# Eload_Gen_3_Power_Module_-_User_Inferfac.net
KiCad netlist of a schematic drawn in Altium Designer
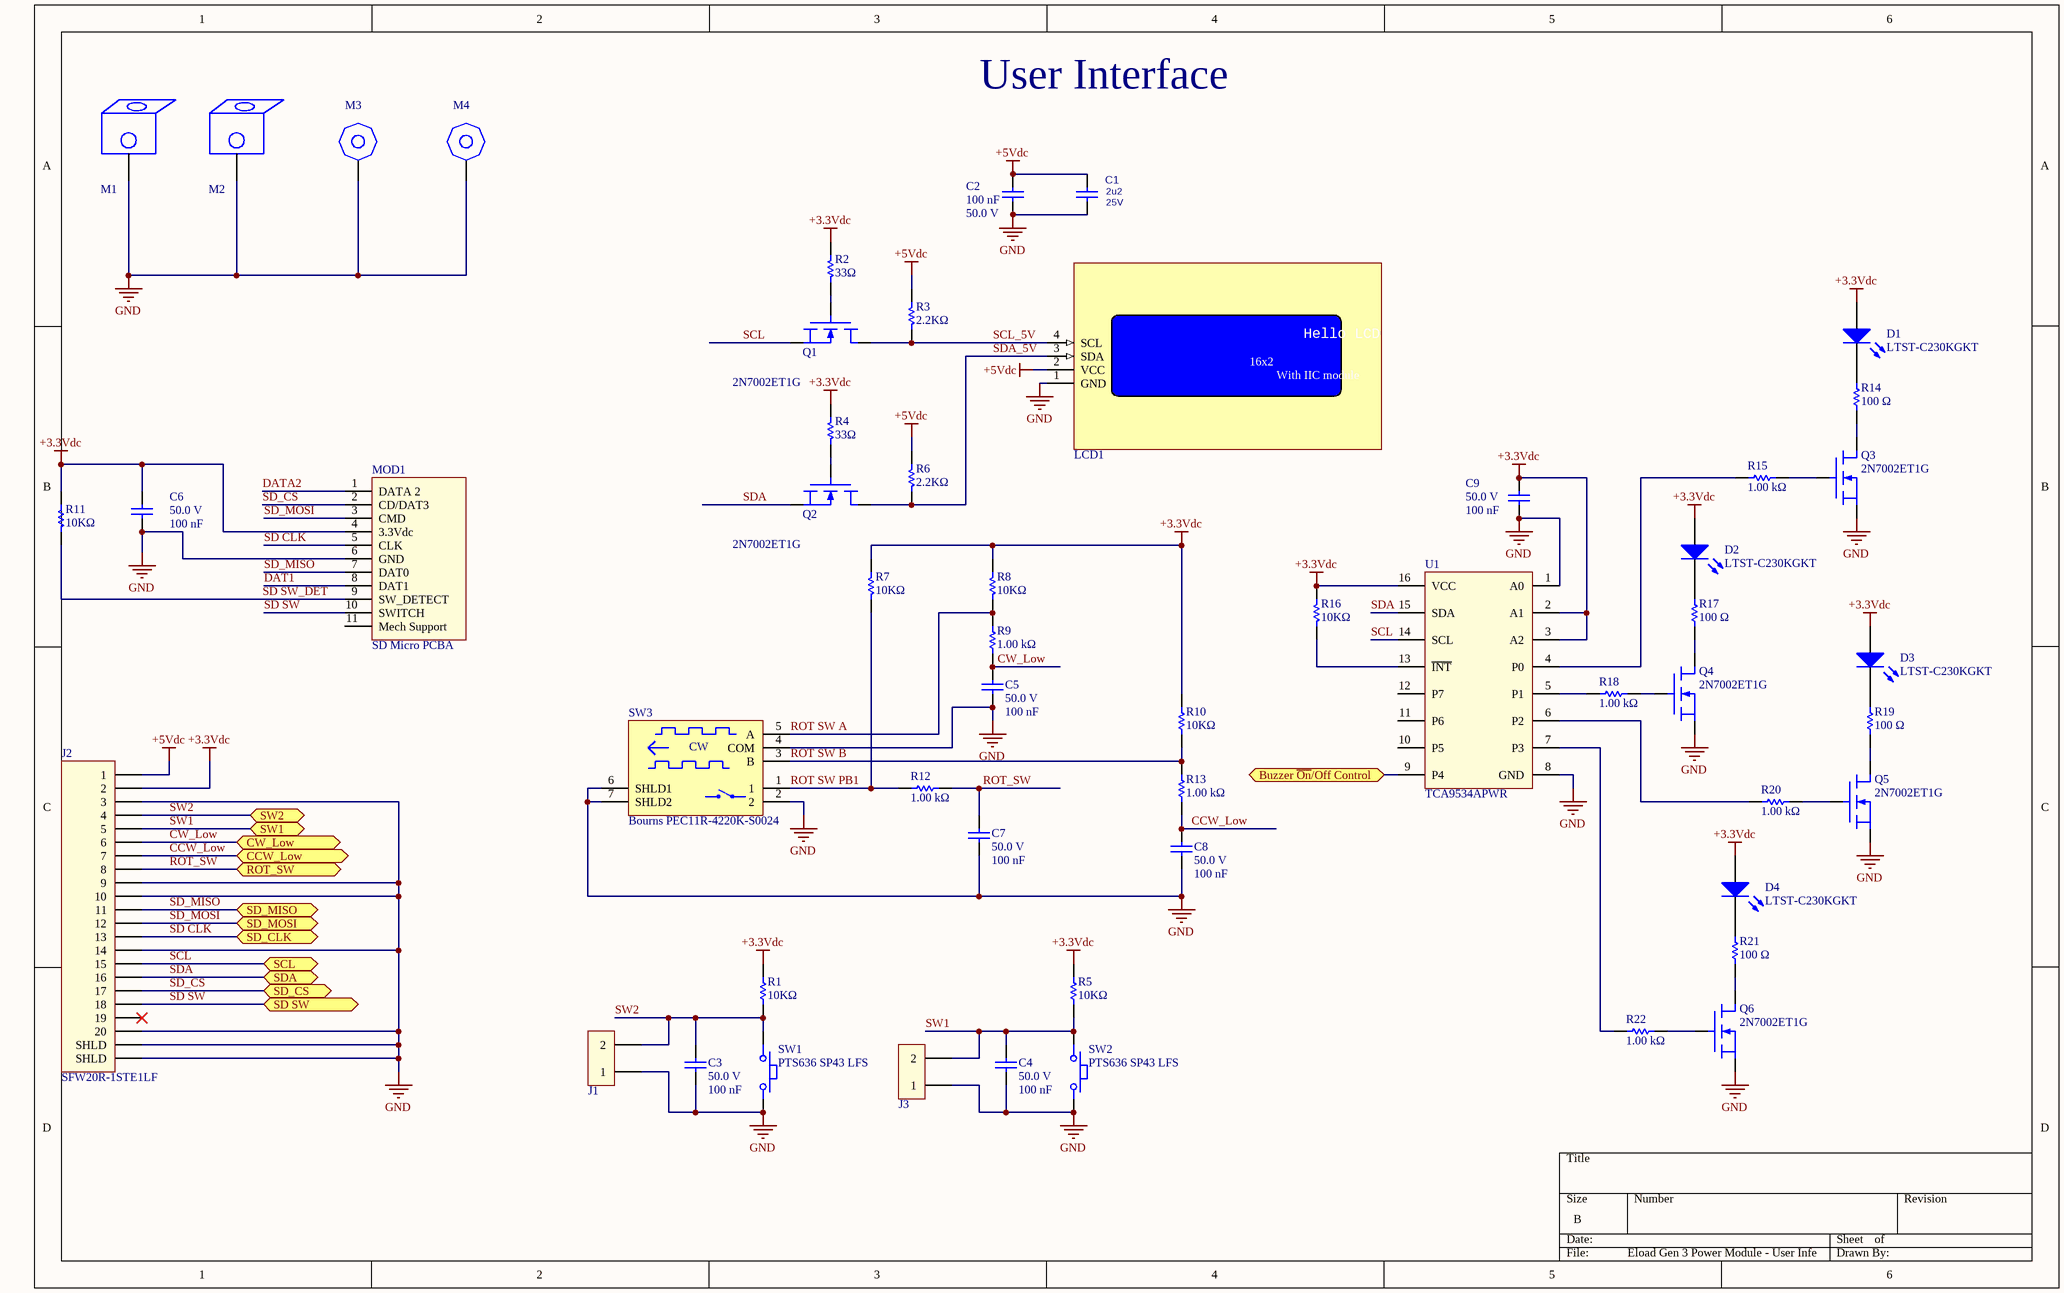
[diagram p0: Eload Gen 3 Power Module - User Inferface Rev 2.SchDoc]

(export (version "E")
  (design (tool "Eeschema 10.0.6"))
  (components
    (comp (ref "C1")
      (value "2u2")
      (footprint "CAP, 0805, HD")
      (description "Cap,SMD,MLCC,2.2uF 25V X7R 10%,0805")
      (fields (field (name "MANUFACTURER") "Murata") (field (name "VOLTAGE") "25V"))
      (libsource (lib "Master SEPT2019") (part "Cap,0805,2.2uF,10%,25V"))
    )
    (comp (ref "C2")
      (value "08055C104JAT2A")
      (footprint "Cap,0805")
      (description "Capacitor; Ceramic; Cap 0.1 uF; Tol 5%; Vol-Rtg 50 VDC; SMT; 0805; X7R; Tape & Reel")
      (fields (field (name "VOLTAGE RATING (DC)") "50.0 V") (field (name "CAPACITANCE") "100 nF"))
      (libsource (lib "Master JULY2019") (part "Cap,0805,100nf,50V,5%,08055C104JAT2A"))
    )
    (comp (ref "C3")
      (value "08055C104JAT2A")
      (footprint "CAP, 0805, HD")
      (description "Capacitor; Ceramic; Cap 0.1 uF; Tol 5%; Vol-Rtg 50 VDC; SMT; 0805; X7R; Tape & Reel")
      (fields (field (name "VOLTAGE RATING (DC)") "50.0 V") (field (name "CAPACITANCE") "100 nF"))
      (libsource (lib "Master JULY2019") (part "Cap,0805,100nf,50V,5%,08055C104JAT2A"))
    )
    (comp (ref "C4")
      (value "08055C104JAT2A")
      (footprint "CAP, 0805, HD")
      (description "Capacitor; Ceramic; Cap 0.1 uF; Tol 5%; Vol-Rtg 50 VDC; SMT; 0805; X7R; Tape & Reel")
      (fields (field (name "VOLTAGE RATING (DC)") "50.0 V") (field (name "CAPACITANCE") "100 nF"))
      (libsource (lib "Master JULY2019") (part "Cap,0805,100nf,50V,5%,08055C104JAT2A"))
    )
    (comp (ref "C5")
      (value "08055C104JAT2A")
      (footprint "CAP, 0805, HD")
      (description "Capacitor; Ceramic; Cap 0.1 uF; Tol 5%; Vol-Rtg 50 VDC; SMT; 0805; X7R; Tape & Reel")
      (fields (field (name "VOLTAGE RATING (DC)") "50.0 V") (field (name "CAPACITANCE") "100 nF"))
      (libsource (lib "Master JULY2019") (part "Cap,0805,100nf,50V,5%,08055C104JAT2A"))
    )
    (comp (ref "C6")
      (value "08055C104JAT2A")
      (footprint "Cap,0805")
      (description "Capacitor; Ceramic; Cap 0.1 uF; Tol 5%; Vol-Rtg 50 VDC; SMT; 0805; X7R; Tape & Reel")
      (fields (field (name "VOLTAGE RATING (DC)") "50.0 V") (field (name "CAPACITANCE") "100 nF"))
      (libsource (lib "Master JULY2019") (part "Cap,0805,100nf,50V,5%,08055C104JAT2A"))
    )
    (comp (ref "C7")
      (value "08055C104JAT2A")
      (footprint "CAP, 0805, HD")
      (description "Capacitor; Ceramic; Cap 0.1 uF; Tol 5%; Vol-Rtg 50 VDC; SMT; 0805; X7R; Tape & Reel")
      (fields (field (name "VOLTAGE RATING (DC)") "50.0 V") (field (name "CAPACITANCE") "100 nF"))
      (libsource (lib "Master JULY2019") (part "Cap,0805,100nf,50V,5%,08055C104JAT2A"))
    )
    (comp (ref "C8")
      (value "08055C104JAT2A")
      (footprint "CAP, 0805, HD")
      (description "Capacitor; Ceramic; Cap 0.1 uF; Tol 5%; Vol-Rtg 50 VDC; SMT; 0805; X7R; Tape & Reel")
      (fields (field (name "VOLTAGE RATING (DC)") "50.0 V") (field (name "CAPACITANCE") "100 nF"))
      (libsource (lib "Master JULY2019") (part "Cap,0805,100nf,50V,5%,08055C104JAT2A"))
    )
    (comp (ref "C9")
      (value "08055C104JAT2A")
      (footprint "Cap,0805")
      (description "Capacitor; Ceramic; Cap 0.1 uF; Tol 5%; Vol-Rtg 50 VDC; SMT; 0805; X7R; Tape & Reel")
      (fields (field (name "VOLTAGE RATING (DC)") "50.0 V") (field (name "CAPACITANCE") "100 nF"))
      (libsource (lib "Master Mar2021") (part "Cap,0805,100nf,50V,5%,08055C104JAT2A"))
    )
    (comp (ref "D1")
      (value "LTST-C230KGKT")
      (footprint "LED,SMD,Bottom Entry,1206")
      (description "LED GREEN CLEAR CHIP SMD")
      (fields (field (name "MANUFACTURER") "Lite-On Inc."))
      (libsource (lib "Master JULY2019") (part "LED,1206,Green,SMD,BtmEnt,LTST-C230KGKT"))
    )
    (comp (ref "D2")
      (value "LTST-C230KGKT")
      (footprint "LED,SMD,Bottom Entry,1206")
      (description "LED GREEN CLEAR CHIP SMD")
      (fields (field (name "MANUFACTURER") "Lite-On Inc."))
      (libsource (lib "Master JULY2019") (part "LED,1206,Green,SMD,BtmEnt,LTST-C230KGKT"))
    )
    (comp (ref "D3")
      (value "LTST-C230KGKT")
      (footprint "LED,SMD,Bottom Entry,1206")
      (description "LED GREEN CLEAR CHIP SMD")
      (fields (field (name "MANUFACTURER") "Lite-On Inc."))
      (libsource (lib "Master JULY2019") (part "LED,1206,Green,SMD,BtmEnt,LTST-C230KGKT"))
    )
    (comp (ref "D4")
      (value "LTST-C230KGKT")
      (footprint "LED,SMD,Bottom Entry,1206")
      (description "LED GREEN CLEAR CHIP SMD")
      (fields (field (name "MANUFACTURER") "Lite-On Inc."))
      (libsource (lib "Master JULY2019") (part "LED,1206,Green,SMD,BtmEnt,LTST-C230KGKT"))
    )
    (comp (ref "J1")
      (value "Generic Header")
      (footprint "HEADER-1X2,0.1\"")
      (libsource (lib "Master JULY2019") (part "Header 1x2,0.1{dblquote}Spacing"))
    )
    (comp (ref "J2")
      (value "SFW20R-1STE1LF")
      (footprint "Connector,FlatFlex,20Pin,RA")
      (description "CONN FFC BOTTOM 20POS 1.00MM R/A")
      (fields (field (name "MANUFACTURER") "Amphenol ICC (FCI)"))
      (libsource (lib "Master JULY2019") (part "Connector,FFC,SMD,20Pin,1mmSpc,SFW20R-1STE1LF"))
    )
    (comp (ref "J3")
      (value "Generic Header")
      (footprint "HEADER-1X2,0.1\"")
      (libsource (lib "Master JULY2019") (part "Header 1x2,0.1{dblquote}Spacing"))
    )
    (comp (ref "LCD1")
      (value "LCD, 20x4")
      (footprint "LCD Module 16x2 - IIC MOD")
      (description "LCD Character Display; 4x20 Char.; 98x60; STN- BLUE; Transmissive; 8-Bit Parallel")
      (libsource (lib "Master JULY2019") (part "LCD, 16x2, IIC"))
    )
    (comp (ref "M1")
      (value "4334")
      (footprint "Mech,Bracket,RA,#6,Threaded")
      (description "Mounting Bracket Short L #6-32 (2) Steel, Nickel Plated")
      (fields (field (name "MANUFACTURER") "Keystone Electronics"))
      (libsource (lib "Master JULY2019") (part "Mech,Bracket,RA,Threaded,4334"))
    )
    (comp (ref "M2")
      (value "4334")
      (footprint "Mech,Bracket,RA,#6,Threaded")
      (description "Mounting Bracket Short L #6-32 (2) Steel, Nickel Plated")
      (fields (field (name "MANUFACTURER") "Keystone Electronics"))
      (libsource (lib "Master JULY2019") (part "Mech,Bracket,RA,Threaded,4334"))
    )
    (comp (ref "M3")
      (value "M3 hex Standoff")
      (footprint "Standoff,Hex,M3,8mm")
      (description "HEX STANDOFF M3,generic")
      (libsource (lib "Master JULY2019") (part "Mech,Standoff, M3, Hex"))
    )
    (comp (ref "M4")
      (value "M3 hex Standoff")
      (footprint "Standoff,Hex,M3,8mm")
      (description "HEX STANDOFF M3,generic")
      (libsource (lib "Master JULY2019") (part "Mech,Standoff, M3, Hex"))
    )
    (comp (ref "MOD1")
      (value "SD Card Connector Breakout")
      (footprint "Mod, SD Card Connector Breakout")
      (fields (field (name "DISCRIPTION") "SD Micro PCBA"))
      (libsource (lib "Master JULY2019") (part "Mod,SD Card breakout, Vertical"))
    )
    (comp (ref "Q1")
      (value "2N7002ET1G")
      (footprint "SOT23-3")
      (description "Small Signal MOSFET, 60 V, 310 mA, Single, N-Channel, 3-Pin SOT-23, Pb-Free, Tape and Reel")
      (fields
        (field (name "MANUFACTURER") "ON Semiconductor")
        (field (name "MANUFACTURER PART NUMBER") "2N7002ET1G")
      )
      (libsource (lib "Master JULY2019") (part "MOSFET,N-Channel,SOT23,0.25A,60V,2N7002ET1G"))
    )
    (comp (ref "Q2")
      (value "2N7002ET1G")
      (footprint "SOT23-3")
      (description "Small Signal MOSFET, 60 V, 310 mA, Single, N-Channel, 3-Pin SOT-23, Pb-Free, Tape and Reel")
      (fields
        (field (name "MANUFACTURER") "ON Semiconductor")
        (field (name "MANUFACTURER PART NUMBER") "2N7002ET1G")
      )
      (libsource (lib "Master JULY2019") (part "MOSFET,N-Channel,SOT23,0.25A,60V,2N7002ET1G"))
    )
    (comp (ref "Q3")
      (value "2N7002ET1G")
      (footprint "SOT23-3")
      (description "Small Signal MOSFET, 60 V, 310 mA, Single, N-Channel, 3-Pin SOT-23, Pb-Free, Tape and Reel")
      (fields
        (field (name "MANUFACTURER") "ON Semiconductor")
        (field (name "MANUFACTURER PART NUMBER") "2N7002ET1G")
      )
      (libsource (lib "Master JULY2019") (part "MOSFET,N-Channel,SOT23,0.25A,60V,2N7002ET1G"))
    )
    (comp (ref "Q4")
      (value "2N7002ET1G")
      (footprint "SOT23-3")
      (description "Small Signal MOSFET, 60 V, 310 mA, Single, N-Channel, 3-Pin SOT-23, Pb-Free, Tape and Reel")
      (fields
        (field (name "MANUFACTURER") "ON Semiconductor")
        (field (name "MANUFACTURER PART NUMBER") "2N7002ET1G")
      )
      (libsource (lib "Master JULY2019") (part "MOSFET,N-Channel,SOT23,0.25A,60V,2N7002ET1G"))
    )
    (comp (ref "Q5")
      (value "2N7002ET1G")
      (footprint "SOT23-3")
      (description "Small Signal MOSFET, 60 V, 310 mA, Single, N-Channel, 3-Pin SOT-23, Pb-Free, Tape and Reel")
      (fields
        (field (name "MANUFACTURER") "ON Semiconductor")
        (field (name "MANUFACTURER PART NUMBER") "2N7002ET1G")
      )
      (libsource (lib "Master JULY2019") (part "MOSFET,N-Channel,SOT23,0.25A,60V,2N7002ET1G"))
    )
    (comp (ref "Q6")
      (value "2N7002ET1G")
      (footprint "SOT23-3")
      (description "Small Signal MOSFET, 60 V, 310 mA, Single, N-Channel, 3-Pin SOT-23, Pb-Free, Tape and Reel")
      (fields
        (field (name "MANUFACTURER") "ON Semiconductor")
        (field (name "MANUFACTURER PART NUMBER") "2N7002ET1G")
      )
      (libsource (lib "Master JULY2019") (part "MOSFET,N-Channel,SOT23,0.25A,60V,2N7002ET1G"))
    )
    (comp (ref "R1")
      (value "Vishay / Dale CRCW080510K0FKTA")
      (footprint "res, 0805, HD")
      (description "RES SMD 10K OHM 1% 1/8W 0805")
      (fields (field (name "RESISTANCE") "10KΩ"))
      (libsource (lib "Master JULY2019") (part "Res,0805,10.0kΩ,1%,100 ppm,CRCW080510K0FKTA"))
    )
    (comp (ref "R2")
      (value "CR0805-JW-330ELF")
      (footprint "res, 0805, HD")
      (description "RES SMD 33 OHM 5% 1/8W 0805")
      (fields
        (field (name "MANUFACTURER") "Bourns Inc.")
        (field (name "TOLERANCE") "±5%")
        (field (name "RESISTANCE") "33Ω")
      )
      (libsource (lib "Master JULY2019") (part "Res,0805,33Ω,±5%,200ppm,CR0805-JW-330ELF"))
    )
    (comp (ref "R3")
      (value "CRCW08052K20FKEA")
      (footprint "res, 0805, HD")
      (description "RES SMD 2.2K OHM 1% 1/8W 0805")
      (fields (field (name "RESISTANCE") "2.2KΩ"))
      (libsource (lib "Master JULY2019") (part "Res,0805,2.2KΩ,±1%,100.0 ppm/°C,150.0 V,CRCW08052K20FKEA"))
    )
    (comp (ref "R4")
      (value "CR0805-JW-330ELF")
      (footprint "res, 0805, HD")
      (description "RES SMD 33 OHM 5% 1/8W 0805")
      (fields
        (field (name "MANUFACTURER") "Bourns Inc.")
        (field (name "TOLERANCE") "±5%")
        (field (name "RESISTANCE") "33Ω")
      )
      (libsource (lib "Master JULY2019") (part "Res,0805,33Ω,±5%,200ppm,CR0805-JW-330ELF"))
    )
    (comp (ref "R5")
      (value "Vishay / Dale CRCW080510K0FKTA")
      (footprint "res, 0805, HD")
      (description "RES SMD 10K OHM 1% 1/8W 0805")
      (fields (field (name "RESISTANCE") "10KΩ"))
      (libsource (lib "Master JULY2019") (part "Res,0805,10.0kΩ,1%,100 ppm,CRCW080510K0FKTA"))
    )
    (comp (ref "R6")
      (value "CRCW08052K20FKEA")
      (footprint "res, 0805, HD")
      (description "RES SMD 2.2K OHM 1% 1/8W 0805")
      (fields (field (name "RESISTANCE") "2.2KΩ"))
      (libsource (lib "Master JULY2019") (part "Res,0805,2.2KΩ,±1%,100.0 ppm/°C,150.0 V,CRCW08052K20FKEA"))
    )
    (comp (ref "R7")
      (value "Vishay / Dale CRCW080510K0FKTA")
      (footprint "res, 0805, HD")
      (description "RES SMD 10K OHM 1% 1/8W 0805")
      (fields (field (name "RESISTANCE") "10KΩ"))
      (libsource (lib "Master JULY2019") (part "Res,0805,10.0kΩ,1%,100 ppm,CRCW080510K0FKTA"))
    )
    (comp (ref "R8")
      (value "Vishay / Dale CRCW080510K0FKTA")
      (footprint "res, 0805, HD")
      (description "RES SMD 10K OHM 1% 1/8W 0805")
      (fields (field (name "RESISTANCE") "10KΩ"))
      (libsource (lib "Master JULY2019") (part "Res,0805,10.0kΩ,1%,100 ppm,CRCW080510K0FKTA"))
    )
    (comp (ref "R9")
      (value "Vishay CRCW08051K00JNEA")
      (footprint "res, 0805, HD")
      (description "Res Thick Film 0805 1K Ohm 5% 0.125W(1/8W) ±200ppm/C Molded SMD Automotive Paper T/R")
      (fields
        (field (name "MANUFACTURER PART NUMBER") "CRCW08051K00JNEA")
        (field (name "RESISTANCE") "1.00 kΩ")
      )
      (libsource (lib "Master JULY2019") (part "Res,0805,1.00 kΩ,5%,200ppm,CRCW08051K00JNEA"))
    )
    (comp (ref "R10")
      (value "Vishay / Dale CRCW080510K0FKTA")
      (footprint "res, 0805, HD")
      (description "RES SMD 10K OHM 1% 1/8W 0805")
      (fields (field (name "RESISTANCE") "10KΩ"))
      (libsource (lib "Master JULY2019") (part "Res,0805,10.0kΩ,1%,100 ppm,CRCW080510K0FKTA"))
    )
    (comp (ref "R11")
      (value "Vishay / Dale CRCW080510K0FKTA")
      (footprint "res, 0805, HD")
      (description "RES SMD 10K OHM 1% 1/8W 0805")
      (fields (field (name "RESISTANCE") "10KΩ"))
      (libsource (lib "Master JULY2019") (part "Res,0805,10.0kΩ,1%,100 ppm,CRCW080510K0FKTA"))
    )
    (comp (ref "R12")
      (value "Vishay CRCW08051K00JNEA")
      (footprint "res, 0805, HD")
      (description "Res Thick Film 0805 1K Ohm 5% 0.125W(1/8W) ±200ppm/C Molded SMD Automotive Paper T/R")
      (fields
        (field (name "MANUFACTURER PART NUMBER") "CRCW08051K00JNEA")
        (field (name "RESISTANCE") "1.00 kΩ")
      )
      (libsource (lib "Master JULY2019") (part "Res,0805,1.00 kΩ,5%,200ppm,CRCW08051K00JNEA"))
    )
    (comp (ref "R13")
      (value "Vishay CRCW08051K00JNEA")
      (footprint "res, 0805, HD")
      (description "Res Thick Film 0805 1K Ohm 5% 0.125W(1/8W) ±200ppm/C Molded SMD Automotive Paper T/R")
      (fields
        (field (name "MANUFACTURER PART NUMBER") "CRCW08051K00JNEA")
        (field (name "RESISTANCE") "1.00 kΩ")
      )
      (libsource (lib "Master JULY2019") (part "Res,0805,1.00 kΩ,5%,200ppm,CRCW08051K00JNEA"))
    )
    (comp (ref "R14")
      (value "CRCW0805100RJNEAC")
      (footprint "res, 0805, HD")
      (description "RES 100 OHM 5% 1/8W 0805")
      (fields (field (name "TOLERANCE") "±5%") (field (name "RESISTANCE") "100 Ω"))
      (libsource (lib "Master JULY2019") (part "Res,0805,100Ω,5%,±200ppm/°C"))
    )
    (comp (ref "R15")
      (value "Vishay CRCW08051K00JNEA")
      (footprint "res, 0805, HD")
      (description "Res Thick Film 0805 1K Ohm 5% 0.125W(1/8W) ±200ppm/C Molded SMD Automotive Paper T/R")
      (fields
        (field (name "MANUFACTURER PART NUMBER") "CRCW08051K00JNEA")
        (field (name "RESISTANCE") "1.00 kΩ")
      )
      (libsource (lib "Master JULY2019") (part "Res,0805,1.00 kΩ,5%,200ppm,CRCW08051K00JNEA"))
    )
    (comp (ref "R16")
      (value "Vishay / Dale CRCW080510K0FKTA")
      (footprint "res, 0805, HD")
      (description "RES SMD 10K OHM 1% 1/8W 0805")
      (fields (field (name "RESISTANCE") "10KΩ"))
      (libsource (lib "Master Mar2021") (part "Res,0805,10.0kΩ,1%,100 ppm,CRCW080510K0FKTA"))
    )
    (comp (ref "R17")
      (value "CRCW0805100RJNEAC")
      (footprint "res, 0805, HD")
      (description "RES 100 OHM 5% 1/8W 0805")
      (fields (field (name "TOLERANCE") "±5%") (field (name "RESISTANCE") "100 Ω"))
      (libsource (lib "Master JULY2019") (part "Res,0805,100Ω,5%,±200ppm/°C"))
    )
    (comp (ref "R18")
      (value "Vishay CRCW08051K00JNEA")
      (footprint "res, 0805, HD")
      (description "Res Thick Film 0805 1K Ohm 5% 0.125W(1/8W) ±200ppm/C Molded SMD Automotive Paper T/R")
      (fields
        (field (name "MANUFACTURER PART NUMBER") "CRCW08051K00JNEA")
        (field (name "RESISTANCE") "1.00 kΩ")
      )
      (libsource (lib "Master Mar2021") (part "Res,0805,1.00 kΩ,5%,200ppm,CRCW08051K00JNEA"))
    )
    (comp (ref "R19")
      (value "CRCW0805100RJNEAC")
      (footprint "res, 0805, HD")
      (description "RES 100 OHM 5% 1/8W 0805")
      (fields (field (name "TOLERANCE") "±5%") (field (name "RESISTANCE") "100 Ω"))
      (libsource (lib "Master JULY2019") (part "Res,0805,100Ω,5%,±200ppm/°C"))
    )
    (comp (ref "R20")
      (value "Vishay CRCW08051K00JNEA")
      (footprint "res, 0805, HD")
      (description "Res Thick Film 0805 1K Ohm 5% 0.125W(1/8W) ±200ppm/C Molded SMD Automotive Paper T/R")
      (fields
        (field (name "MANUFACTURER PART NUMBER") "CRCW08051K00JNEA")
        (field (name "RESISTANCE") "1.00 kΩ")
      )
      (libsource (lib "Master JULY2019") (part "Res,0805,1.00 kΩ,5%,200ppm,CRCW08051K00JNEA"))
    )
    (comp (ref "R21")
      (value "CRCW0805100RJNEAC")
      (footprint "res, 0805, HD")
      (description "RES 100 OHM 5% 1/8W 0805")
      (fields (field (name "TOLERANCE") "±5%") (field (name "RESISTANCE") "100 Ω"))
      (libsource (lib "Master JULY2019") (part "Res,0805,100Ω,5%,±200ppm/°C"))
    )
    (comp (ref "R22")
      (value "Vishay CRCW08051K00JNEA")
      (footprint "res, 0805, HD")
      (description "Res Thick Film 0805 1K Ohm 5% 0.125W(1/8W) ±200ppm/C Molded SMD Automotive Paper T/R")
      (fields
        (field (name "MANUFACTURER PART NUMBER") "CRCW08051K00JNEA")
        (field (name "RESISTANCE") "1.00 kΩ")
      )
      (libsource (lib "Master JULY2019") (part "Res,0805,1.00 kΩ,5%,200ppm,CRCW08051K00JNEA"))
    )
    (comp (ref "SW1")
      (value "PTS636 SP43 LFS")
      (footprint "PTS636 SP43 LFS")
      (description "Tactile Switch SPST-NO Top Actuated Through Hole")
      (fields (field (name "MANUFACTURER") "C&K"))
      (libsource (lib "Master JULY2019") (part "Switch,Through Hole,Tactile,SPST-NO,PTS636 SP43 LFS"))
    )
    (comp (ref "SW2")
      (value "PTS636 SP43 LFS")
      (footprint "PTS636 SP43 LFS")
      (description "Tactile Switch SPST-NO Top Actuated Through Hole")
      (fields (field (name "MANUFACTURER") "C&K"))
      (libsource (lib "Master JULY2019") (part "Switch,Through Hole,Tactile,SPST-NO,PTS636 SP43 LFS"))
    )
    (comp (ref "SW3")
      (value "Bourns PEC11R-4220K-S0024")
      (footprint "Rotary encoder")
      (description "24 Pulse Incremental Mechanical Rotary Encoder w/ 6 mm Knurl Shaft, Through Hole")
      (libsource (lib "Master JULY2019") (part "Rotary encoder, PEC11R-4220K-S0024"))
    )
    (comp (ref "U1")
      (value "TCA9534APWR")
      (footprint "TSSOP-16")
      (description "IC I/O EXPANDER I2C 8B 16TSSOP")
      (fields (field (name "MANUFACTURER") "Texas Instruments") (field (name "BASE PART NUMBER") "TCA953"))
      (libsource (lib "Master Mar2021") (part "IC,IO Expander,IIC,8IO,16-TSSOP,TCA9534APWR"))
    )
  )
  (nets
    (net (code "1") (name "+3.3Vdc") (class "Default")
      (node (ref "C6") (pin "2") (pinfunction "2_2") (pintype "passive"))
      (node (ref "C9") (pin "2") (pinfunction "2_2") (pintype "passive"))
      (node (ref "D1") (pin "2") (pinfunction "A_2") (pintype "passive"))
      (node (ref "D2") (pin "2") (pinfunction "A_2") (pintype "passive"))
      (node (ref "D3") (pin "2") (pinfunction "A_2") (pintype "passive"))
      (node (ref "D4") (pin "2") (pinfunction "A_2") (pintype "passive"))
      (node (ref "J2") (pin "2") (pinfunction "2_2") (pintype "passive"))
      (node (ref "MOD1") (pin "4") (pinfunction "3.3Vdc_4") (pintype "passive"))
      (node (ref "R1") (pin "1") (pinfunction "1_1") (pintype "passive"))
      (node (ref "R10") (pin "1") (pinfunction "1_1") (pintype "passive"))
      (node (ref "R11") (pin "1") (pinfunction "1_1") (pintype "passive"))
      (node (ref "R16") (pin "2") (pinfunction "2_2") (pintype "passive"))
      (node (ref "R2") (pin "1") (pinfunction "1_1") (pintype "passive"))
      (node (ref "R4") (pin "1") (pinfunction "1_1") (pintype "passive"))
      (node (ref "R5") (pin "1") (pinfunction "1_1") (pintype "passive"))
      (node (ref "R7") (pin "2") (pinfunction "2_2") (pintype "passive"))
      (node (ref "R8") (pin "2") (pinfunction "2_2") (pintype "passive"))
      (node (ref "U1") (pin "16") (pinfunction "VCC_16") (pintype "passive"))
      (node (ref "U1") (pin "2") (pinfunction "A1_2") (pintype "passive"))
      (node (ref "U1") (pin "3") (pinfunction "A2_3") (pintype "passive"))
    )
    (net (code "2") (name "+5Vdc") (class "Default")
      (node (ref "C1") (pin "2") (pintype "passive"))
      (node (ref "C2") (pin "2") (pinfunction "2_2") (pintype "passive"))
      (node (ref "J2") (pin "1") (pinfunction "1_1") (pintype "passive"))
      (node (ref "LCD1") (pin "2") (pinfunction "VCC_2") (pintype "power_in"))
      (node (ref "R3") (pin "2") (pinfunction "2_2") (pintype "passive"))
      (node (ref "R6") (pin "2") (pinfunction "2_2") (pintype "passive"))
    )
    (net (code "3") (name "/Buzzer ~{On}{slash}Off Control") (class "Default")
      (node (ref "U1") (pin "9") (pinfunction "P4_9") (pintype "passive"))
    )
    (net (code "4") (name "/CCW_Low") (class "Default")
      (node (ref "C8") (pin "2") (pinfunction "2_2") (pintype "passive"))
      (node (ref "J2") (pin "7") (pinfunction "7_7") (pintype "passive"))
      (node (ref "R13") (pin "2") (pinfunction "2_2") (pintype "passive"))
    )
    (net (code "5") (name "/CW_Low") (class "Default")
      (node (ref "C5") (pin "2") (pinfunction "2_2") (pintype "passive"))
      (node (ref "J2") (pin "6") (pinfunction "6_6") (pintype "passive"))
      (node (ref "R9") (pin "2") (pinfunction "2_2") (pintype "passive"))
    )
    (net (code "6") (name "/DAT1") (class "Default")
      (node (ref "MOD1") (pin "8") (pinfunction "DAT1_8") (pintype "passive"))
    )
    (net (code "7") (name "/DATA2") (class "Default")
      (node (ref "MOD1") (pin "1") (pinfunction "DATA_2_1") (pintype "passive"))
    )
    (net (code "8") (name "/ROT SW A") (class "Default")
      (node (ref "R8") (pin "1") (pinfunction "1_1") (pintype "passive"))
      (node (ref "R9") (pin "1") (pinfunction "1_1") (pintype "passive"))
      (node (ref "SW3") (pin "5") (pinfunction "A_5") (pintype "passive"))
    )
    (net (code "9") (name "/ROT SW B") (class "Default")
      (node (ref "R10") (pin "2") (pinfunction "2_2") (pintype "passive"))
      (node (ref "R13") (pin "1") (pinfunction "1_1") (pintype "passive"))
      (node (ref "SW3") (pin "3") (pinfunction "B_3") (pintype "passive"))
    )
    (net (code "10") (name "/ROT SW PB1") (class "Default")
      (node (ref "R12") (pin "1") (pinfunction "1_1") (pintype "passive"))
      (node (ref "R7") (pin "1") (pinfunction "1_1") (pintype "passive"))
      (node (ref "SW3") (pin "1") (pinfunction "1_1") (pintype "passive"))
    )
    (net (code "11") (name "/ROT_SW") (class "Default")
      (node (ref "C7") (pin "2") (pinfunction "2_2") (pintype "passive"))
      (node (ref "J2") (pin "8") (pinfunction "8_8") (pintype "passive"))
      (node (ref "R12") (pin "2") (pinfunction "2_2") (pintype "passive"))
    )
    (net (code "12") (name "/SCL") (class "Default")
      (node (ref "J2") (pin "15") (pinfunction "15_15") (pintype "passive"))
      (node (ref "Q1") (pin "2") (pinfunction "S_2") (pintype "passive"))
      (node (ref "U1") (pin "14") (pinfunction "SCL_14") (pintype "passive"))
    )
    (net (code "13") (name "/SCL_5V") (class "Default")
      (node (ref "LCD1") (pin "4") (pinfunction "SCL_4") (pintype "input"))
      (node (ref "Q1") (pin "3") (pinfunction "D_3") (pintype "passive"))
      (node (ref "R3") (pin "1") (pinfunction "1_1") (pintype "passive"))
    )
    (net (code "14") (name "/SD CLK") (class "Default")
      (node (ref "J2") (pin "13") (pinfunction "13_13") (pintype "passive"))
      (node (ref "MOD1") (pin "5") (pinfunction "CLK_5") (pintype "passive"))
    )
    (net (code "15") (name "/SD SW") (class "Default")
      (node (ref "J2") (pin "18") (pinfunction "18_18") (pintype "passive"))
      (node (ref "MOD1") (pin "10") (pinfunction "SWITCH_10") (pintype "passive"))
    )
    (net (code "16") (name "/SD SW_DET") (class "Default")
      (node (ref "MOD1") (pin "9") (pinfunction "SW_DETECT_9") (pintype "passive"))
      (node (ref "R11") (pin "2") (pinfunction "2_2") (pintype "passive"))
    )
    (net (code "17") (name "/SDA") (class "Default")
      (node (ref "J2") (pin "16") (pinfunction "16_16") (pintype "passive"))
      (node (ref "Q2") (pin "2") (pinfunction "S_2") (pintype "passive"))
      (node (ref "U1") (pin "15") (pinfunction "SDA_15") (pintype "passive"))
    )
    (net (code "18") (name "/SDA_5V") (class "Default")
      (node (ref "LCD1") (pin "3") (pinfunction "SDA_3") (pintype "input"))
      (node (ref "Q2") (pin "3") (pinfunction "D_3") (pintype "passive"))
      (node (ref "R6") (pin "1") (pinfunction "1_1") (pintype "passive"))
    )
    (net (code "19") (name "/SD_CS") (class "Default")
      (node (ref "J2") (pin "17") (pinfunction "17_17") (pintype "passive"))
      (node (ref "MOD1") (pin "2") (pinfunction "CD/DAT3_2") (pintype "passive"))
    )
    (net (code "20") (name "/SD_MISO") (class "Default")
      (node (ref "J2") (pin "11") (pinfunction "11_11") (pintype "passive"))
      (node (ref "MOD1") (pin "7") (pinfunction "DAT0_7") (pintype "passive"))
    )
    (net (code "21") (name "/SD_MOSI") (class "Default")
      (node (ref "J2") (pin "12") (pinfunction "12_12") (pintype "passive"))
      (node (ref "MOD1") (pin "3") (pinfunction "CMD_3") (pintype "passive"))
    )
    (net (code "22") (name "/SW1") (class "Default")
      (node (ref "C4") (pin "2") (pinfunction "2_2") (pintype "passive"))
      (node (ref "J2") (pin "5") (pinfunction "5_5") (pintype "passive"))
      (node (ref "J3") (pin "2") (pinfunction "2_2") (pintype "passive"))
      (node (ref "R5") (pin "2") (pinfunction "2_2") (pintype "passive"))
      (node (ref "SW2") (pin "1") (pinfunction "1_1") (pintype "passive"))
    )
    (net (code "23") (name "/SW2") (class "Default")
      (node (ref "C3") (pin "2") (pinfunction "2_2") (pintype "passive"))
      (node (ref "J1") (pin "2") (pinfunction "2_2") (pintype "passive"))
      (node (ref "J2") (pin "4") (pinfunction "4_4") (pintype "passive"))
      (node (ref "R1") (pin "2") (pinfunction "2_2") (pintype "passive"))
      (node (ref "SW1") (pin "1") (pinfunction "1_1") (pintype "passive"))
    )
    (net (code "24") (name "GND") (class "Default")
      (node (ref "C1") (pin "1") (pintype "passive"))
      (node (ref "C2") (pin "1") (pinfunction "1_1") (pintype "passive"))
      (node (ref "C3") (pin "1") (pinfunction "1_1") (pintype "passive"))
      (node (ref "C4") (pin "1") (pinfunction "1_1") (pintype "passive"))
      (node (ref "C5") (pin "1") (pinfunction "1_1") (pintype "passive"))
      (node (ref "C6") (pin "1") (pinfunction "1_1") (pintype "passive"))
      (node (ref "C7") (pin "1") (pinfunction "1_1") (pintype "passive"))
      (node (ref "C8") (pin "1") (pinfunction "1_1") (pintype "passive"))
      (node (ref "C9") (pin "1") (pinfunction "1_1") (pintype "passive"))
      (node (ref "J1") (pin "1") (pinfunction "1_1") (pintype "passive"))
      (node (ref "J2") (pin "10") (pinfunction "10_10") (pintype "passive"))
      (node (ref "J2") (pin "14") (pinfunction "14_14") (pintype "passive"))
      (node (ref "J2") (pin "20") (pinfunction "20_20") (pintype "passive"))
      (node (ref "J2") (pin "21") (pinfunction "SHLD_21") (pintype "passive"))
      (node (ref "J2") (pin "22") (pinfunction "SHLD_22") (pintype "passive"))
      (node (ref "J2") (pin "3") (pinfunction "3_3") (pintype "passive"))
      (node (ref "J2") (pin "9") (pinfunction "9_9") (pintype "passive"))
      (node (ref "J3") (pin "1") (pinfunction "1_1") (pintype "passive"))
      (node (ref "LCD1") (pin "1") (pinfunction "GND_1") (pintype "power_in"))
      (node (ref "M1") (pin "1") (pinfunction "1_1") (pintype "passive"))
      (node (ref "M2") (pin "1") (pinfunction "1_1") (pintype "passive"))
      (node (ref "M3") (pin "0") (pinfunction "0_0") (pintype "passive"))
      (node (ref "M4") (pin "0") (pinfunction "0_0") (pintype "passive"))
      (node (ref "MOD1") (pin "6") (pinfunction "GND_6") (pintype "passive"))
      (node (ref "Q3") (pin "2") (pinfunction "S_2") (pintype "passive"))
      (node (ref "Q4") (pin "2") (pinfunction "S_2") (pintype "passive"))
      (node (ref "Q5") (pin "2") (pinfunction "S_2") (pintype "passive"))
      (node (ref "Q6") (pin "2") (pinfunction "S_2") (pintype "passive"))
      (node (ref "SW1") (pin "2") (pinfunction "2_2") (pintype "passive"))
      (node (ref "SW2") (pin "2") (pinfunction "2_2") (pintype "passive"))
      (node (ref "SW3") (pin "2") (pinfunction "2_2") (pintype "passive"))
      (node (ref "SW3") (pin "4") (pinfunction "COM_4") (pintype "passive"))
      (node (ref "SW3") (pin "6") (pinfunction "SHLD1_6") (pintype "passive"))
      (node (ref "SW3") (pin "7") (pinfunction "SHLD2_7") (pintype "passive"))
      (node (ref "U1") (pin "1") (pinfunction "A0_1") (pintype "passive"))
      (node (ref "U1") (pin "8") (pinfunction "GND_8") (pintype "passive"))
    )
    (net (code "25") (name "Net-(D1-K)") (class "Default")
      (node (ref "D1") (pin "1") (pinfunction "K_1") (pintype "passive"))
      (node (ref "R14") (pin "2") (pinfunction "2_2") (pintype "passive"))
    )
    (net (code "26") (name "Net-(D2-K)") (class "Default")
      (node (ref "D2") (pin "1") (pinfunction "K_1") (pintype "passive"))
      (node (ref "R17") (pin "2") (pinfunction "2_2") (pintype "passive"))
    )
    (net (code "27") (name "Net-(D3-K)") (class "Default")
      (node (ref "D3") (pin "1") (pinfunction "K_1") (pintype "passive"))
      (node (ref "R19") (pin "2") (pinfunction "2_2") (pintype "passive"))
    )
    (net (code "28") (name "Net-(D4-K)") (class "Default")
      (node (ref "D4") (pin "1") (pinfunction "K_1") (pintype "passive"))
      (node (ref "R21") (pin "2") (pinfunction "2_2") (pintype "passive"))
    )
    (net (code "29") (name "Net-(Q1-G)") (class "Default")
      (node (ref "Q1") (pin "1") (pinfunction "G_1") (pintype "passive"))
      (node (ref "R2") (pin "2") (pinfunction "2_2") (pintype "passive"))
    )
    (net (code "30") (name "Net-(Q2-G)") (class "Default")
      (node (ref "Q2") (pin "1") (pinfunction "G_1") (pintype "passive"))
      (node (ref "R4") (pin "2") (pinfunction "2_2") (pintype "passive"))
    )
    (net (code "31") (name "Net-(Q3-D)") (class "Default")
      (node (ref "Q3") (pin "3") (pinfunction "D_3") (pintype "passive"))
      (node (ref "R14") (pin "1") (pinfunction "1_1") (pintype "passive"))
    )
    (net (code "32") (name "Net-(Q3-G)") (class "Default")
      (node (ref "Q3") (pin "1") (pinfunction "G_1") (pintype "passive"))
      (node (ref "R15") (pin "2") (pinfunction "2_2") (pintype "passive"))
    )
    (net (code "33") (name "Net-(Q4-D)") (class "Default")
      (node (ref "Q4") (pin "3") (pinfunction "D_3") (pintype "passive"))
      (node (ref "R17") (pin "1") (pinfunction "1_1") (pintype "passive"))
    )
    (net (code "34") (name "Net-(Q4-G)") (class "Default")
      (node (ref "Q4") (pin "1") (pinfunction "G_1") (pintype "passive"))
      (node (ref "R18") (pin "2") (pinfunction "2_2") (pintype "passive"))
    )
    (net (code "35") (name "Net-(Q5-D)") (class "Default")
      (node (ref "Q5") (pin "3") (pinfunction "D_3") (pintype "passive"))
      (node (ref "R19") (pin "1") (pinfunction "1_1") (pintype "passive"))
    )
    (net (code "36") (name "Net-(Q5-G)") (class "Default")
      (node (ref "Q5") (pin "1") (pinfunction "G_1") (pintype "passive"))
      (node (ref "R20") (pin "2") (pinfunction "2_2") (pintype "passive"))
    )
    (net (code "37") (name "Net-(Q6-D)") (class "Default")
      (node (ref "Q6") (pin "3") (pinfunction "D_3") (pintype "passive"))
      (node (ref "R21") (pin "1") (pinfunction "1_1") (pintype "passive"))
    )
    (net (code "38") (name "Net-(Q6-G)") (class "Default")
      (node (ref "Q6") (pin "1") (pinfunction "G_1") (pintype "passive"))
      (node (ref "R22") (pin "2") (pinfunction "2_2") (pintype "passive"))
    )
    (net (code "39") (name "Net-(U1-P0)") (class "Default")
      (node (ref "R15") (pin "1") (pinfunction "1_1") (pintype "passive"))
      (node (ref "U1") (pin "4") (pinfunction "P0_4") (pintype "passive"))
    )
    (net (code "40") (name "Net-(U1-P1)") (class "Default")
      (node (ref "R18") (pin "1") (pinfunction "1_1") (pintype "passive"))
      (node (ref "U1") (pin "5") (pinfunction "P1_5") (pintype "passive"))
    )
    (net (code "41") (name "Net-(U1-P2)") (class "Default")
      (node (ref "R20") (pin "1") (pinfunction "1_1") (pintype "passive"))
      (node (ref "U1") (pin "6") (pinfunction "P2_6") (pintype "passive"))
    )
    (net (code "42") (name "Net-(U1-P3)") (class "Default")
      (node (ref "R22") (pin "1") (pinfunction "1_1") (pintype "passive"))
      (node (ref "U1") (pin "7") (pinfunction "P3_7") (pintype "passive"))
    )
    (net (code "43") (name "Net-(U1-~{INT})") (class "Default")
      (node (ref "R16") (pin "1") (pinfunction "1_1") (pintype "passive"))
      (node (ref "U1") (pin "13") (pinfunction "~{INT}_13") (pintype "passive"))
    )
    (net (code "44") (name "unconnected-(J2-Pad19)") (class "Default")
      (node (ref "J2") (pin "19") (pinfunction "19_19") (pintype "passive+no_connect"))
    )
    (net (code "45") (name "unconnected-(MOD1-Mech_Support-Pad11)") (class "Default")
      (node (ref "MOD1") (pin "11") (pinfunction "Mech_Support_11") (pintype "passive"))
    )
    (net (code "46") (name "unconnected-(U1-P5-Pad10)") (class "Default")
      (node (ref "U1") (pin "10") (pinfunction "P5_10") (pintype "passive"))
    )
    (net (code "47") (name "unconnected-(U1-P6-Pad11)") (class "Default")
      (node (ref "U1") (pin "11") (pinfunction "P6_11") (pintype "passive"))
    )
    (net (code "48") (name "unconnected-(U1-P7-Pad12)") (class "Default")
      (node (ref "U1") (pin "12") (pinfunction "P7_12") (pintype "passive"))
    )
  )
)
